# BME280-Breakout_v10.net
KiCad netlist of a schematic drawn in EAGLE
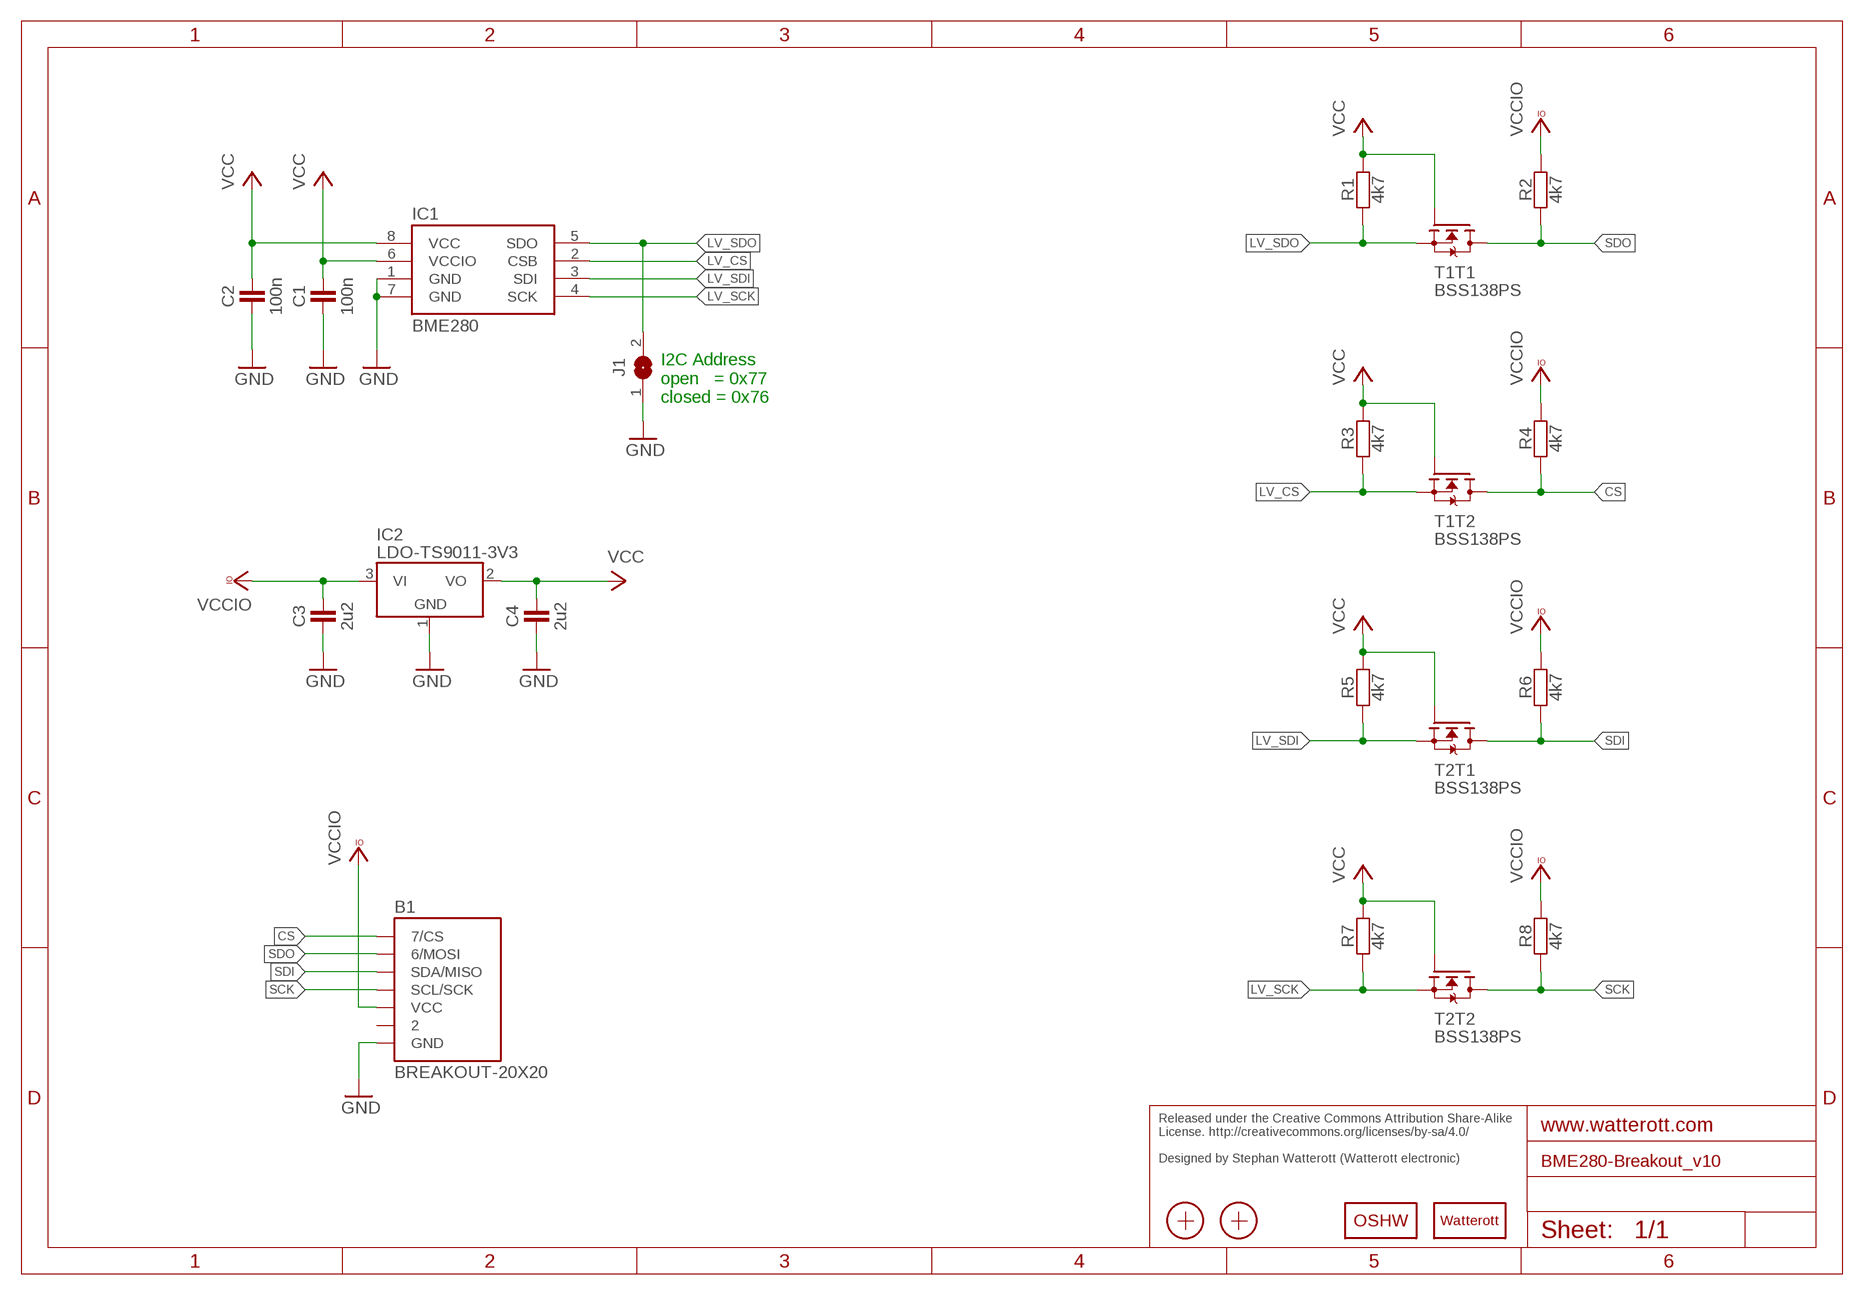
[diagram p0: schematic, sheet 1]

(export (version "E")
  (design (tool "Eeschema 10.0.6"))
  (components
    (comp (ref "B1")
      (value "BREAKOUT-20X20")
      (footprint "eagle-import:BREAKOUT-20X20")
      (libsource (lib "eagle-import") (part "BREAKOUT-20X20"))
    )
    (comp (ref "C1")
      (value "100n")
      (footprint "eagle-import:C0402")
      (libsource (lib "eagle-import") (part "CAPACITOR-0402"))
    )
    (comp (ref "C2")
      (value "100n")
      (footprint "eagle-import:C0402")
      (libsource (lib "eagle-import") (part "CAPACITOR-0402"))
    )
    (comp (ref "C3")
      (value "2u2")
      (footprint "eagle-import:C0402")
      (libsource (lib "eagle-import") (part "CAPACITOR-0402"))
    )
    (comp (ref "C4")
      (value "2u2")
      (footprint "eagle-import:C0402")
      (libsource (lib "eagle-import") (part "CAPACITOR-0402"))
    )
    (comp (ref "IC1")
      (value "BME280")
      (footprint "eagle-import:CAVITY_MEMS")
      (libsource (lib "eagle-import") (part "BME280"))
    )
    (comp (ref "IC2")
      (value "LDO-TS9011-3V3")
      (footprint "eagle-import:SOT23")
      (libsource (lib "eagle-import") (part "LDO-TS9011-3V3"))
    )
    (comp (ref "J1")
      (value "JUMPER2-0603")
      (footprint "eagle-import:JUMPER2-0603")
      (libsource (lib "eagle-import") (part "JUMPER2-0603"))
    )
    (comp (ref "LOGO1")
      (value "LOGO-S_PLACE_S")
      (footprint "eagle-import:SPARK_TPLACE_S")
      (libsource (lib "eagle-import") (part "LOGO-S_PLACE_S"))
    )
    (comp (ref "LOGO2")
      (value "OSHW_LOGOX0070")
      (footprint "eagle-import:OSHW_6X70")
      (libsource (lib "eagle-import") (part "OSHW_LOGOX0070"))
    )
    (comp (ref "R1")
      (value "4k7")
      (footprint "eagle-import:C0402")
      (libsource (lib "eagle-import") (part "RESISTOR-0402"))
    )
    (comp (ref "R2")
      (value "4k7")
      (footprint "eagle-import:C0402")
      (libsource (lib "eagle-import") (part "RESISTOR-0402"))
    )
    (comp (ref "R3")
      (value "4k7")
      (footprint "eagle-import:C0402")
      (libsource (lib "eagle-import") (part "RESISTOR-0402"))
    )
    (comp (ref "R4")
      (value "4k7")
      (footprint "eagle-import:C0402")
      (libsource (lib "eagle-import") (part "RESISTOR-0402"))
    )
    (comp (ref "R5")
      (value "4k7")
      (footprint "eagle-import:C0402")
      (libsource (lib "eagle-import") (part "RESISTOR-0402"))
    )
    (comp (ref "R6")
      (value "4k7")
      (footprint "eagle-import:C0402")
      (libsource (lib "eagle-import") (part "RESISTOR-0402"))
    )
    (comp (ref "R7")
      (value "4k7")
      (footprint "eagle-import:C0402")
      (libsource (lib "eagle-import") (part "RESISTOR-0402"))
    )
    (comp (ref "R8")
      (value "4k7")
      (footprint "eagle-import:C0402")
      (libsource (lib "eagle-import") (part "RESISTOR-0402"))
    )
    (comp (ref "T1")
      (value "BSS138PS")
      (footprint "eagle-import:SOT363")
      (libsource (lib "eagle-import") (part "BSS138PS"))
    )
    (comp (ref "T2")
      (value "BSS138PS")
      (footprint "eagle-import:SOT363")
      (libsource (lib "eagle-import") (part "BSS138PS"))
    )
    (comp (ref "X1")
      (value "PASSER-07")
      (footprint "eagle-import:PASSER_07MM")
      (libsource (lib "eagle-import") (part "PASSER-07"))
    )
    (comp (ref "X2")
      (value "PASSER-07")
      (footprint "eagle-import:PASSER_07MM")
      (libsource (lib "eagle-import") (part "PASSER-07"))
    )
  )
  (nets
    (net (code "1") (name "CS") (class "Default")
      (node (ref "B1") (pin "CS") (pinfunction "7/CS_CS") (pintype "bidirectional"))
      (node (ref "R4") (pin "1") (pinfunction "1_1") (pintype "passive"))
      (node (ref "T1") (pin "3") (pinfunction "D_3") (pintype "passive"))
    )
    (net (code "2") (name "GND") (class "Default")
      (node (ref "B1") (pin "GND") (pinfunction "GND_GND") (pintype "power_in"))
      (node (ref "C1") (pin "1") (pinfunction "1_1") (pintype "passive"))
      (node (ref "C2") (pin "1") (pinfunction "1_1") (pintype "passive"))
      (node (ref "C3") (pin "1") (pinfunction "1_1") (pintype "passive"))
      (node (ref "C4") (pin "1") (pinfunction "1_1") (pintype "passive"))
      (node (ref "IC1") (pin "1") (pinfunction "GND_1") (pintype "power_in"))
      (node (ref "IC1") (pin "7") (pinfunction "GND_7") (pintype "power_in"))
      (node (ref "IC2") (pin "1") (pinfunction "GND_1") (pintype "passive"))
      (node (ref "J1") (pin "1") (pinfunction "1_1") (pintype "passive"))
    )
    (net (code "3") (name "LV_CS") (class "Default")
      (node (ref "IC1") (pin "2") (pinfunction "CSB_2") (pintype "input"))
      (node (ref "R3") (pin "1") (pinfunction "1_1") (pintype "passive"))
      (node (ref "T1") (pin "4") (pinfunction "S_4") (pintype "passive"))
    )
    (net (code "4") (name "LV_SCK") (class "Default")
      (node (ref "IC1") (pin "4") (pinfunction "SCK_4") (pintype "bidirectional"))
      (node (ref "R7") (pin "1") (pinfunction "1_1") (pintype "passive"))
      (node (ref "T2") (pin "4") (pinfunction "S_4") (pintype "passive"))
    )
    (net (code "5") (name "LV_SDI") (class "Default")
      (node (ref "IC1") (pin "3") (pinfunction "SDI_3") (pintype "bidirectional"))
      (node (ref "R5") (pin "1") (pinfunction "1_1") (pintype "passive"))
      (node (ref "T2") (pin "1") (pinfunction "S_1") (pintype "passive"))
    )
    (net (code "6") (name "LV_SDO") (class "Default")
      (node (ref "IC1") (pin "5") (pinfunction "SDO_5") (pintype "bidirectional"))
      (node (ref "J1") (pin "2") (pinfunction "2_2") (pintype "passive"))
      (node (ref "R1") (pin "1") (pinfunction "1_1") (pintype "passive"))
      (node (ref "T1") (pin "1") (pinfunction "S_1") (pintype "passive"))
    )
    (net (code "7") (name "SCK") (class "Default")
      (node (ref "B1") (pin "SCL/SCK") (pinfunction "SCL/SCK_SCL/SCK") (pintype "bidirectional"))
      (node (ref "R8") (pin "1") (pinfunction "1_1") (pintype "passive"))
      (node (ref "T2") (pin "3") (pinfunction "D_3") (pintype "passive"))
    )
    (net (code "8") (name "SDI") (class "Default")
      (node (ref "B1") (pin "SDA/MISO") (pinfunction "SDA/MISO_SDA/MISO") (pintype "bidirectional"))
      (node (ref "R6") (pin "1") (pinfunction "1_1") (pintype "passive"))
      (node (ref "T2") (pin "6") (pinfunction "D_6") (pintype "passive"))
    )
    (net (code "9") (name "SDO") (class "Default")
      (node (ref "B1") (pin "MOSI") (pinfunction "6/MOSI_MOSI") (pintype "bidirectional"))
      (node (ref "R2") (pin "1") (pinfunction "1_1") (pintype "passive"))
      (node (ref "T1") (pin "6") (pinfunction "D_6") (pintype "passive"))
    )
    (net (code "10") (name "VCC") (class "Default")
      (node (ref "C1") (pin "2") (pinfunction "2_2") (pintype "passive"))
      (node (ref "C2") (pin "2") (pinfunction "2_2") (pintype "passive"))
      (node (ref "C4") (pin "2") (pinfunction "2_2") (pintype "passive"))
      (node (ref "IC1") (pin "6") (pinfunction "VCCIO_6") (pintype "power_in"))
      (node (ref "IC1") (pin "8") (pinfunction "VCC_8") (pintype "power_in"))
      (node (ref "IC2") (pin "2") (pinfunction "VO_2") (pintype "passive"))
      (node (ref "R1") (pin "2") (pinfunction "2_2") (pintype "passive"))
      (node (ref "R3") (pin "2") (pinfunction "2_2") (pintype "passive"))
      (node (ref "R5") (pin "2") (pinfunction "2_2") (pintype "passive"))
      (node (ref "R7") (pin "2") (pinfunction "2_2") (pintype "passive"))
      (node (ref "T1") (pin "2") (pinfunction "G_2") (pintype "passive"))
      (node (ref "T1") (pin "5") (pinfunction "G_5") (pintype "passive"))
      (node (ref "T2") (pin "2") (pinfunction "G_2") (pintype "passive"))
      (node (ref "T2") (pin "5") (pinfunction "G_5") (pintype "passive"))
    )
    (net (code "11") (name "VCCIO") (class "Default")
      (node (ref "B1") (pin "VCC") (pinfunction "VCC_VCC") (pintype "power_in"))
      (node (ref "C3") (pin "2") (pinfunction "2_2") (pintype "passive"))
      (node (ref "IC2") (pin "3") (pinfunction "VI_3") (pintype "input"))
      (node (ref "R2") (pin "2") (pinfunction "2_2") (pintype "passive"))
      (node (ref "R4") (pin "2") (pinfunction "2_2") (pintype "passive"))
      (node (ref "R6") (pin "2") (pinfunction "2_2") (pintype "passive"))
      (node (ref "R8") (pin "2") (pinfunction "2_2") (pintype "passive"))
    )
    (net (code "12") (name "unconnected-(B1-Pad2)") (class "Default")
      (node (ref "B1") (pin "2") (pinfunction "2_2") (pintype "bidirectional"))
    )
  )
)
